# support_mega_2560_R3_-_sh_matics.net
KiCad netlist of a schematic drawn in EasyEDA
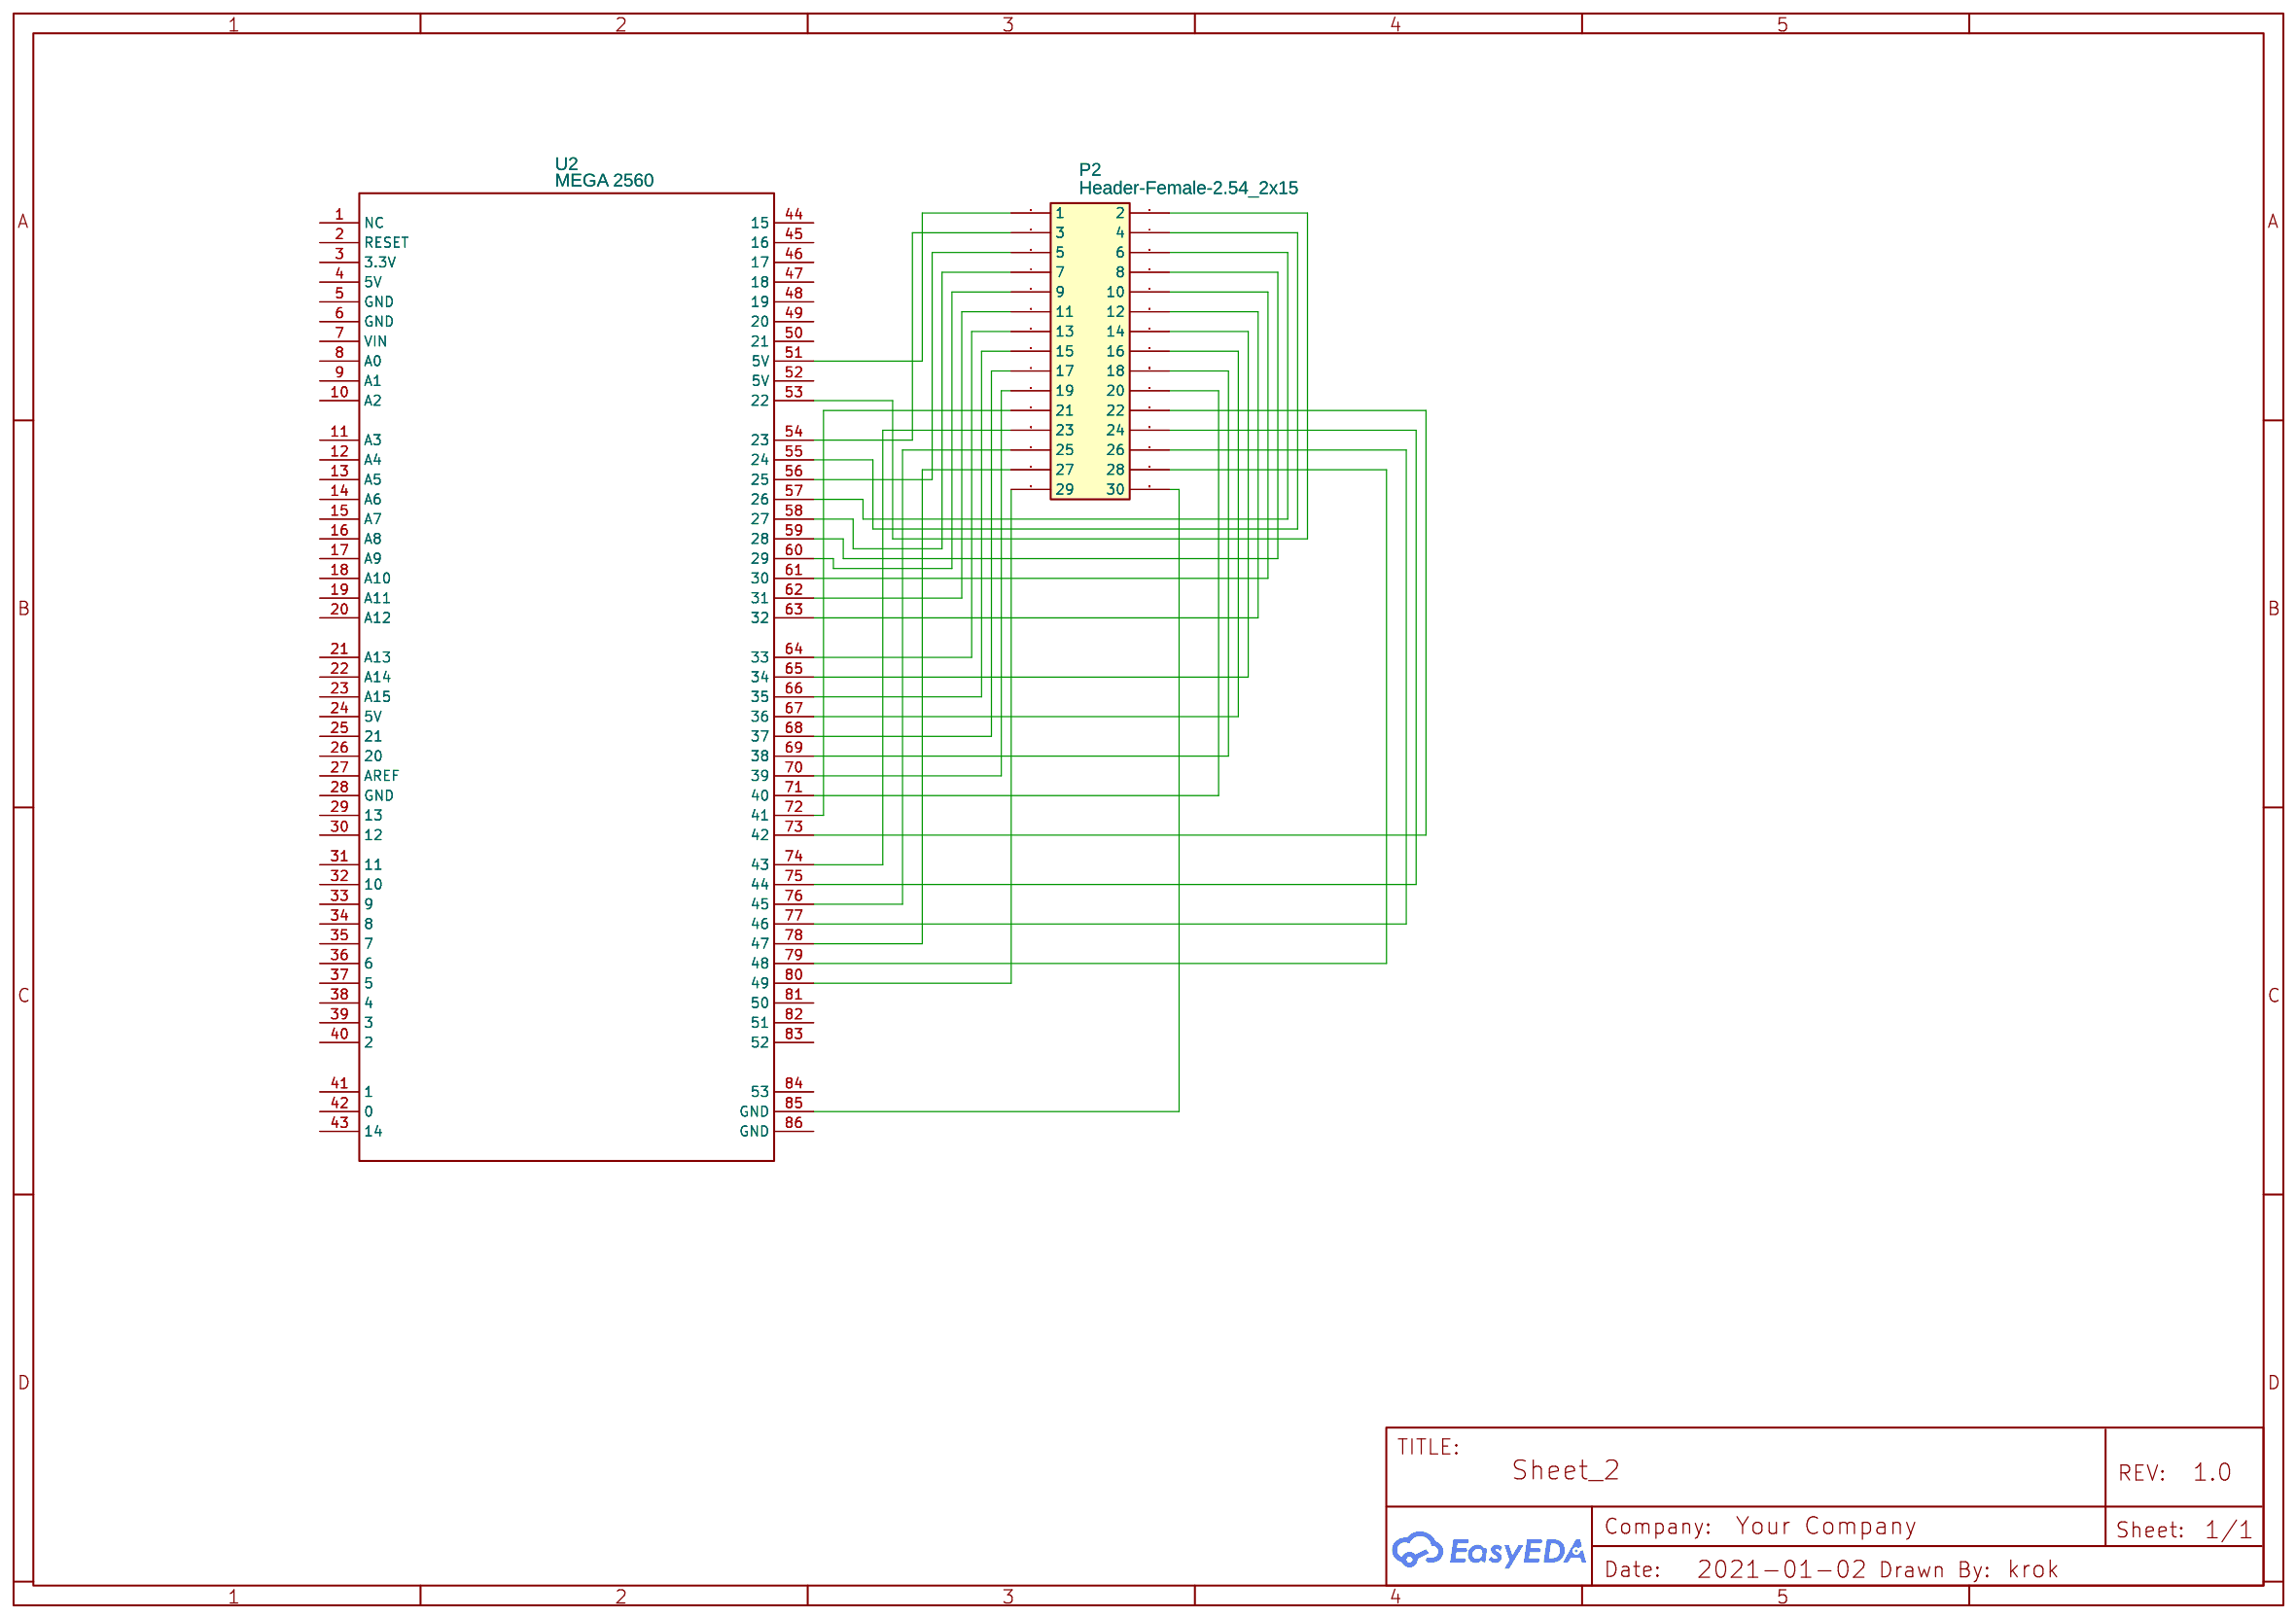
[diagram p0: schematic sheet]

(export (version "E")
  (design (tool "Eeschema 10.0.6"))
  (components
    (comp (ref "P2")
      (value "Header-Female-2.54_2x15")
      (fields (field (name "BOM_Supplier Part") "E58377"))
      (libsource (lib "") (part "Header-Female-2.54_2x15"))
    )
    (comp (ref "U2") (value "MEGA 2560") (libsource (lib "") (part "MEGA 2560")))
  )
  (nets
    (net (code "1") (name "Net-(P2-Pad1)") (class "Default")
      (node (ref "P2") (pin "1") (pinfunction "1_1") (pintype "input"))
      (node (ref "U2") (pin "51") (pinfunction "5V_51") (pintype "unspecified"))
    )
    (net (code "2") (name "Net-(P2-Pad30)") (class "Default")
      (node (ref "P2") (pin "30") (pinfunction "30_30") (pintype "input"))
      (node (ref "U2") (pin "85") (pinfunction "GND_85") (pintype "unspecified"))
    )
    (net (code "3") (name "Net-(U2-22)") (class "Default")
      (node (ref "P2") (pin "2") (pinfunction "2_2") (pintype "input"))
      (node (ref "U2") (pin "53") (pinfunction "22_53") (pintype "unspecified"))
    )
    (net (code "4") (name "Net-(U2-23)") (class "Default")
      (node (ref "P2") (pin "3") (pinfunction "3_3") (pintype "input"))
      (node (ref "U2") (pin "54") (pinfunction "23_54") (pintype "unspecified"))
    )
    (net (code "5") (name "Net-(U2-24)") (class "Default")
      (node (ref "P2") (pin "4") (pinfunction "4_4") (pintype "input"))
      (node (ref "U2") (pin "55") (pinfunction "24_55") (pintype "unspecified"))
    )
    (net (code "6") (name "Net-(U2-25)") (class "Default")
      (node (ref "P2") (pin "5") (pinfunction "5_5") (pintype "input"))
      (node (ref "U2") (pin "56") (pinfunction "25_56") (pintype "unspecified"))
    )
    (net (code "7") (name "Net-(U2-26)") (class "Default")
      (node (ref "P2") (pin "6") (pinfunction "6_6") (pintype "input"))
      (node (ref "U2") (pin "57") (pinfunction "26_57") (pintype "unspecified"))
    )
    (net (code "8") (name "Net-(U2-27)") (class "Default")
      (node (ref "P2") (pin "7") (pinfunction "7_7") (pintype "input"))
      (node (ref "U2") (pin "58") (pinfunction "27_58") (pintype "unspecified"))
    )
    (net (code "9") (name "Net-(U2-28)") (class "Default")
      (node (ref "P2") (pin "8") (pinfunction "8_8") (pintype "input"))
      (node (ref "U2") (pin "59") (pinfunction "28_59") (pintype "unspecified"))
    )
    (net (code "10") (name "Net-(U2-29)") (class "Default")
      (node (ref "P2") (pin "9") (pinfunction "9_9") (pintype "input"))
      (node (ref "U2") (pin "60") (pinfunction "29_60") (pintype "unspecified"))
    )
    (net (code "11") (name "Net-(U2-30)") (class "Default")
      (node (ref "P2") (pin "10") (pinfunction "10_10") (pintype "input"))
      (node (ref "U2") (pin "61") (pinfunction "30_61") (pintype "unspecified"))
    )
    (net (code "12") (name "Net-(U2-31)") (class "Default")
      (node (ref "P2") (pin "11") (pinfunction "11_11") (pintype "input"))
      (node (ref "U2") (pin "62") (pinfunction "31_62") (pintype "unspecified"))
    )
    (net (code "13") (name "Net-(U2-32)") (class "Default")
      (node (ref "P2") (pin "12") (pinfunction "12_12") (pintype "input"))
      (node (ref "U2") (pin "63") (pinfunction "32_63") (pintype "unspecified"))
    )
    (net (code "14") (name "Net-(U2-33)") (class "Default")
      (node (ref "P2") (pin "13") (pinfunction "13_13") (pintype "input"))
      (node (ref "U2") (pin "64") (pinfunction "33_64") (pintype "unspecified"))
    )
    (net (code "15") (name "Net-(U2-34)") (class "Default")
      (node (ref "P2") (pin "14") (pinfunction "14_14") (pintype "input"))
      (node (ref "U2") (pin "65") (pinfunction "34_65") (pintype "unspecified"))
    )
    (net (code "16") (name "Net-(U2-35)") (class "Default")
      (node (ref "P2") (pin "15") (pinfunction "15_15") (pintype "input"))
      (node (ref "U2") (pin "66") (pinfunction "35_66") (pintype "unspecified"))
    )
    (net (code "17") (name "Net-(U2-36)") (class "Default")
      (node (ref "P2") (pin "16") (pinfunction "16_16") (pintype "input"))
      (node (ref "U2") (pin "67") (pinfunction "36_67") (pintype "unspecified"))
    )
    (net (code "18") (name "Net-(U2-37)") (class "Default")
      (node (ref "P2") (pin "17") (pinfunction "17_17") (pintype "input"))
      (node (ref "U2") (pin "68") (pinfunction "37_68") (pintype "unspecified"))
    )
    (net (code "19") (name "Net-(U2-38)") (class "Default")
      (node (ref "P2") (pin "18") (pinfunction "18_18") (pintype "input"))
      (node (ref "U2") (pin "69") (pinfunction "38_69") (pintype "unspecified"))
    )
    (net (code "20") (name "Net-(U2-39)") (class "Default")
      (node (ref "P2") (pin "19") (pinfunction "19_19") (pintype "input"))
      (node (ref "U2") (pin "70") (pinfunction "39_70") (pintype "unspecified"))
    )
    (net (code "21") (name "Net-(U2-40)") (class "Default")
      (node (ref "P2") (pin "20") (pinfunction "20_20") (pintype "input"))
      (node (ref "U2") (pin "71") (pinfunction "40_71") (pintype "unspecified"))
    )
    (net (code "22") (name "Net-(U2-41)") (class "Default")
      (node (ref "P2") (pin "21") (pinfunction "21_21") (pintype "input"))
      (node (ref "U2") (pin "72") (pinfunction "41_72") (pintype "unspecified"))
    )
    (net (code "23") (name "Net-(U2-42)") (class "Default")
      (node (ref "P2") (pin "22") (pinfunction "22_22") (pintype "input"))
      (node (ref "U2") (pin "73") (pinfunction "42_73") (pintype "unspecified"))
    )
    (net (code "24") (name "Net-(U2-43)") (class "Default")
      (node (ref "P2") (pin "23") (pinfunction "23_23") (pintype "input"))
      (node (ref "U2") (pin "74") (pinfunction "43_74") (pintype "unspecified"))
    )
    (net (code "25") (name "Net-(U2-44)") (class "Default")
      (node (ref "P2") (pin "24") (pinfunction "24_24") (pintype "input"))
      (node (ref "U2") (pin "75") (pinfunction "44_75") (pintype "unspecified"))
    )
    (net (code "26") (name "Net-(U2-45)") (class "Default")
      (node (ref "P2") (pin "25") (pinfunction "25_25") (pintype "input"))
      (node (ref "U2") (pin "76") (pinfunction "45_76") (pintype "unspecified"))
    )
    (net (code "27") (name "Net-(U2-46)") (class "Default")
      (node (ref "P2") (pin "26") (pinfunction "26_26") (pintype "input"))
      (node (ref "U2") (pin "77") (pinfunction "46_77") (pintype "unspecified"))
    )
    (net (code "28") (name "Net-(U2-47)") (class "Default")
      (node (ref "P2") (pin "27") (pinfunction "27_27") (pintype "input"))
      (node (ref "U2") (pin "78") (pinfunction "47_78") (pintype "unspecified"))
    )
    (net (code "29") (name "Net-(U2-48)") (class "Default")
      (node (ref "P2") (pin "28") (pinfunction "28_28") (pintype "input"))
      (node (ref "U2") (pin "79") (pinfunction "48_79") (pintype "unspecified"))
    )
    (net (code "30") (name "Net-(U2-49)") (class "Default")
      (node (ref "P2") (pin "29") (pinfunction "29_29") (pintype "input"))
      (node (ref "U2") (pin "80") (pinfunction "49_80") (pintype "unspecified"))
    )
    (net (code "31") (name "unconnected-(U2-0-Pad42)") (class "Default")
      (node (ref "U2") (pin "42") (pinfunction "0_42") (pintype "unspecified"))
    )
    (net (code "32") (name "unconnected-(U2-1-Pad41)") (class "Default")
      (node (ref "U2") (pin "41") (pinfunction "1_41") (pintype "unspecified"))
    )
    (net (code "33") (name "unconnected-(U2-2-Pad40)") (class "Default")
      (node (ref "U2") (pin "40") (pinfunction "2_40") (pintype "unspecified"))
    )
    (net (code "34") (name "unconnected-(U2-3-Pad39)") (class "Default")
      (node (ref "U2") (pin "39") (pinfunction "3_39") (pintype "unspecified"))
    )
    (net (code "35") (name "unconnected-(U2-3.3V-Pad3)") (class "Default")
      (node (ref "U2") (pin "3") (pinfunction "3.3V_3") (pintype "unspecified"))
    )
    (net (code "36") (name "unconnected-(U2-4-Pad38)") (class "Default")
      (node (ref "U2") (pin "38") (pinfunction "4_38") (pintype "unspecified"))
    )
    (net (code "37") (name "unconnected-(U2-5-Pad37)") (class "Default")
      (node (ref "U2") (pin "37") (pinfunction "5_37") (pintype "unspecified"))
    )
    (net (code "38") (name "unconnected-(U2-5V-Pad4)") (class "Default")
      (node (ref "U2") (pin "4") (pinfunction "5V_4") (pintype "unspecified"))
    )
    (net (code "39") (name "unconnected-(U2-5V-Pad24)") (class "Default")
      (node (ref "U2") (pin "24") (pinfunction "5V_24") (pintype "unspecified"))
    )
    (net (code "40") (name "unconnected-(U2-5V-Pad52)") (class "Default")
      (node (ref "U2") (pin "52") (pinfunction "5V_52") (pintype "unspecified"))
    )
    (net (code "41") (name "unconnected-(U2-6-Pad36)") (class "Default")
      (node (ref "U2") (pin "36") (pinfunction "6_36") (pintype "unspecified"))
    )
    (net (code "42") (name "unconnected-(U2-7-Pad35)") (class "Default")
      (node (ref "U2") (pin "35") (pinfunction "7_35") (pintype "unspecified"))
    )
    (net (code "43") (name "unconnected-(U2-8-Pad34)") (class "Default")
      (node (ref "U2") (pin "34") (pinfunction "8_34") (pintype "unspecified"))
    )
    (net (code "44") (name "unconnected-(U2-9-Pad33)") (class "Default")
      (node (ref "U2") (pin "33") (pinfunction "9_33") (pintype "unspecified"))
    )
    (net (code "45") (name "unconnected-(U2-10-Pad32)") (class "Default")
      (node (ref "U2") (pin "32") (pinfunction "10_32") (pintype "unspecified"))
    )
    (net (code "46") (name "unconnected-(U2-11-Pad31)") (class "Default")
      (node (ref "U2") (pin "31") (pinfunction "11_31") (pintype "unspecified"))
    )
    (net (code "47") (name "unconnected-(U2-12-Pad30)") (class "Default")
      (node (ref "U2") (pin "30") (pinfunction "12_30") (pintype "unspecified"))
    )
    (net (code "48") (name "unconnected-(U2-13-Pad29)") (class "Default")
      (node (ref "U2") (pin "29") (pinfunction "13_29") (pintype "unspecified"))
    )
    (net (code "49") (name "unconnected-(U2-14-Pad43)") (class "Default")
      (node (ref "U2") (pin "43") (pinfunction "14_43") (pintype "unspecified"))
    )
    (net (code "50") (name "unconnected-(U2-15-Pad44)") (class "Default")
      (node (ref "U2") (pin "44") (pinfunction "15_44") (pintype "unspecified"))
    )
    (net (code "51") (name "unconnected-(U2-16-Pad45)") (class "Default")
      (node (ref "U2") (pin "45") (pinfunction "16_45") (pintype "unspecified"))
    )
    (net (code "52") (name "unconnected-(U2-17-Pad46)") (class "Default")
      (node (ref "U2") (pin "46") (pinfunction "17_46") (pintype "unspecified"))
    )
    (net (code "53") (name "unconnected-(U2-18-Pad47)") (class "Default")
      (node (ref "U2") (pin "47") (pinfunction "18_47") (pintype "unspecified"))
    )
    (net (code "54") (name "unconnected-(U2-19-Pad48)") (class "Default")
      (node (ref "U2") (pin "48") (pinfunction "19_48") (pintype "unspecified"))
    )
    (net (code "55") (name "unconnected-(U2-20-Pad26)") (class "Default")
      (node (ref "U2") (pin "26") (pinfunction "20_26") (pintype "unspecified"))
    )
    (net (code "56") (name "unconnected-(U2-20-Pad49)") (class "Default")
      (node (ref "U2") (pin "49") (pinfunction "20_49") (pintype "unspecified"))
    )
    (net (code "57") (name "unconnected-(U2-21-Pad25)") (class "Default")
      (node (ref "U2") (pin "25") (pinfunction "21_25") (pintype "unspecified"))
    )
    (net (code "58") (name "unconnected-(U2-21-Pad50)") (class "Default")
      (node (ref "U2") (pin "50") (pinfunction "21_50") (pintype "unspecified"))
    )
    (net (code "59") (name "unconnected-(U2-50-Pad81)") (class "Default")
      (node (ref "U2") (pin "81") (pinfunction "50_81") (pintype "unspecified"))
    )
    (net (code "60") (name "unconnected-(U2-51-Pad82)") (class "Default")
      (node (ref "U2") (pin "82") (pinfunction "51_82") (pintype "unspecified"))
    )
    (net (code "61") (name "unconnected-(U2-52-Pad83)") (class "Default")
      (node (ref "U2") (pin "83") (pinfunction "52_83") (pintype "unspecified"))
    )
    (net (code "62") (name "unconnected-(U2-53-Pad84)") (class "Default")
      (node (ref "U2") (pin "84") (pinfunction "53_84") (pintype "unspecified"))
    )
    (net (code "63") (name "unconnected-(U2-A0-Pad8)") (class "Default")
      (node (ref "U2") (pin "8") (pinfunction "A0_8") (pintype "unspecified"))
    )
    (net (code "64") (name "unconnected-(U2-A1-Pad9)") (class "Default")
      (node (ref "U2") (pin "9") (pinfunction "A1_9") (pintype "unspecified"))
    )
    (net (code "65") (name "unconnected-(U2-A2-Pad10)") (class "Default")
      (node (ref "U2") (pin "10") (pinfunction "A2_10") (pintype "unspecified"))
    )
    (net (code "66") (name "unconnected-(U2-A3-Pad11)") (class "Default")
      (node (ref "U2") (pin "11") (pinfunction "A3_11") (pintype "unspecified"))
    )
    (net (code "67") (name "unconnected-(U2-A4-Pad12)") (class "Default")
      (node (ref "U2") (pin "12") (pinfunction "A4_12") (pintype "unspecified"))
    )
    (net (code "68") (name "unconnected-(U2-A5-Pad13)") (class "Default")
      (node (ref "U2") (pin "13") (pinfunction "A5_13") (pintype "unspecified"))
    )
    (net (code "69") (name "unconnected-(U2-A6-Pad14)") (class "Default")
      (node (ref "U2") (pin "14") (pinfunction "A6_14") (pintype "unspecified"))
    )
    (net (code "70") (name "unconnected-(U2-A7-Pad15)") (class "Default")
      (node (ref "U2") (pin "15") (pinfunction "A7_15") (pintype "unspecified"))
    )
    (net (code "71") (name "unconnected-(U2-A8-Pad16)") (class "Default")
      (node (ref "U2") (pin "16") (pinfunction "A8_16") (pintype "unspecified"))
    )
    (net (code "72") (name "unconnected-(U2-A9-Pad17)") (class "Default")
      (node (ref "U2") (pin "17") (pinfunction "A9_17") (pintype "unspecified"))
    )
    (net (code "73") (name "unconnected-(U2-A10-Pad18)") (class "Default")
      (node (ref "U2") (pin "18") (pinfunction "A10_18") (pintype "unspecified"))
    )
    (net (code "74") (name "unconnected-(U2-A11-Pad19)") (class "Default")
      (node (ref "U2") (pin "19") (pinfunction "A11_19") (pintype "unspecified"))
    )
    (net (code "75") (name "unconnected-(U2-A12-Pad20)") (class "Default")
      (node (ref "U2") (pin "20") (pinfunction "A12_20") (pintype "unspecified"))
    )
    (net (code "76") (name "unconnected-(U2-A13-Pad21)") (class "Default")
      (node (ref "U2") (pin "21") (pinfunction "A13_21") (pintype "unspecified"))
    )
    (net (code "77") (name "unconnected-(U2-A14-Pad22)") (class "Default")
      (node (ref "U2") (pin "22") (pinfunction "A14_22") (pintype "unspecified"))
    )
    (net (code "78") (name "unconnected-(U2-A15-Pad23)") (class "Default")
      (node (ref "U2") (pin "23") (pinfunction "A15_23") (pintype "unspecified"))
    )
    (net (code "79") (name "unconnected-(U2-AREF-Pad27)") (class "Default")
      (node (ref "U2") (pin "27") (pinfunction "AREF_27") (pintype "unspecified"))
    )
    (net (code "80") (name "unconnected-(U2-GND-Pad5)") (class "Default")
      (node (ref "U2") (pin "5") (pinfunction "GND_5") (pintype "unspecified"))
    )
    (net (code "81") (name "unconnected-(U2-GND-Pad6)") (class "Default")
      (node (ref "U2") (pin "6") (pinfunction "GND_6") (pintype "unspecified"))
    )
    (net (code "82") (name "unconnected-(U2-GND-Pad28)") (class "Default")
      (node (ref "U2") (pin "28") (pinfunction "GND_28") (pintype "unspecified"))
    )
    (net (code "83") (name "unconnected-(U2-GND-Pad86)") (class "Default")
      (node (ref "U2") (pin "86") (pinfunction "GND_86") (pintype "unspecified"))
    )
    (net (code "84") (name "unconnected-(U2-NC-Pad1)") (class "Default")
      (node (ref "U2") (pin "1") (pinfunction "NC_1") (pintype "unspecified"))
    )
    (net (code "85") (name "unconnected-(U2-RESET-Pad2)") (class "Default")
      (node (ref "U2") (pin "2") (pinfunction "RESET_2") (pintype "unspecified"))
    )
    (net (code "86") (name "unconnected-(U2-VIN-Pad7)") (class "Default")
      (node (ref "U2") (pin "7") (pinfunction "VIN_7") (pintype "unspecified"))
    )
  )
)
